# Custom_Stm_Board_v1_1.net
KiCad netlist of a schematic drawn in EasyEDA Pro
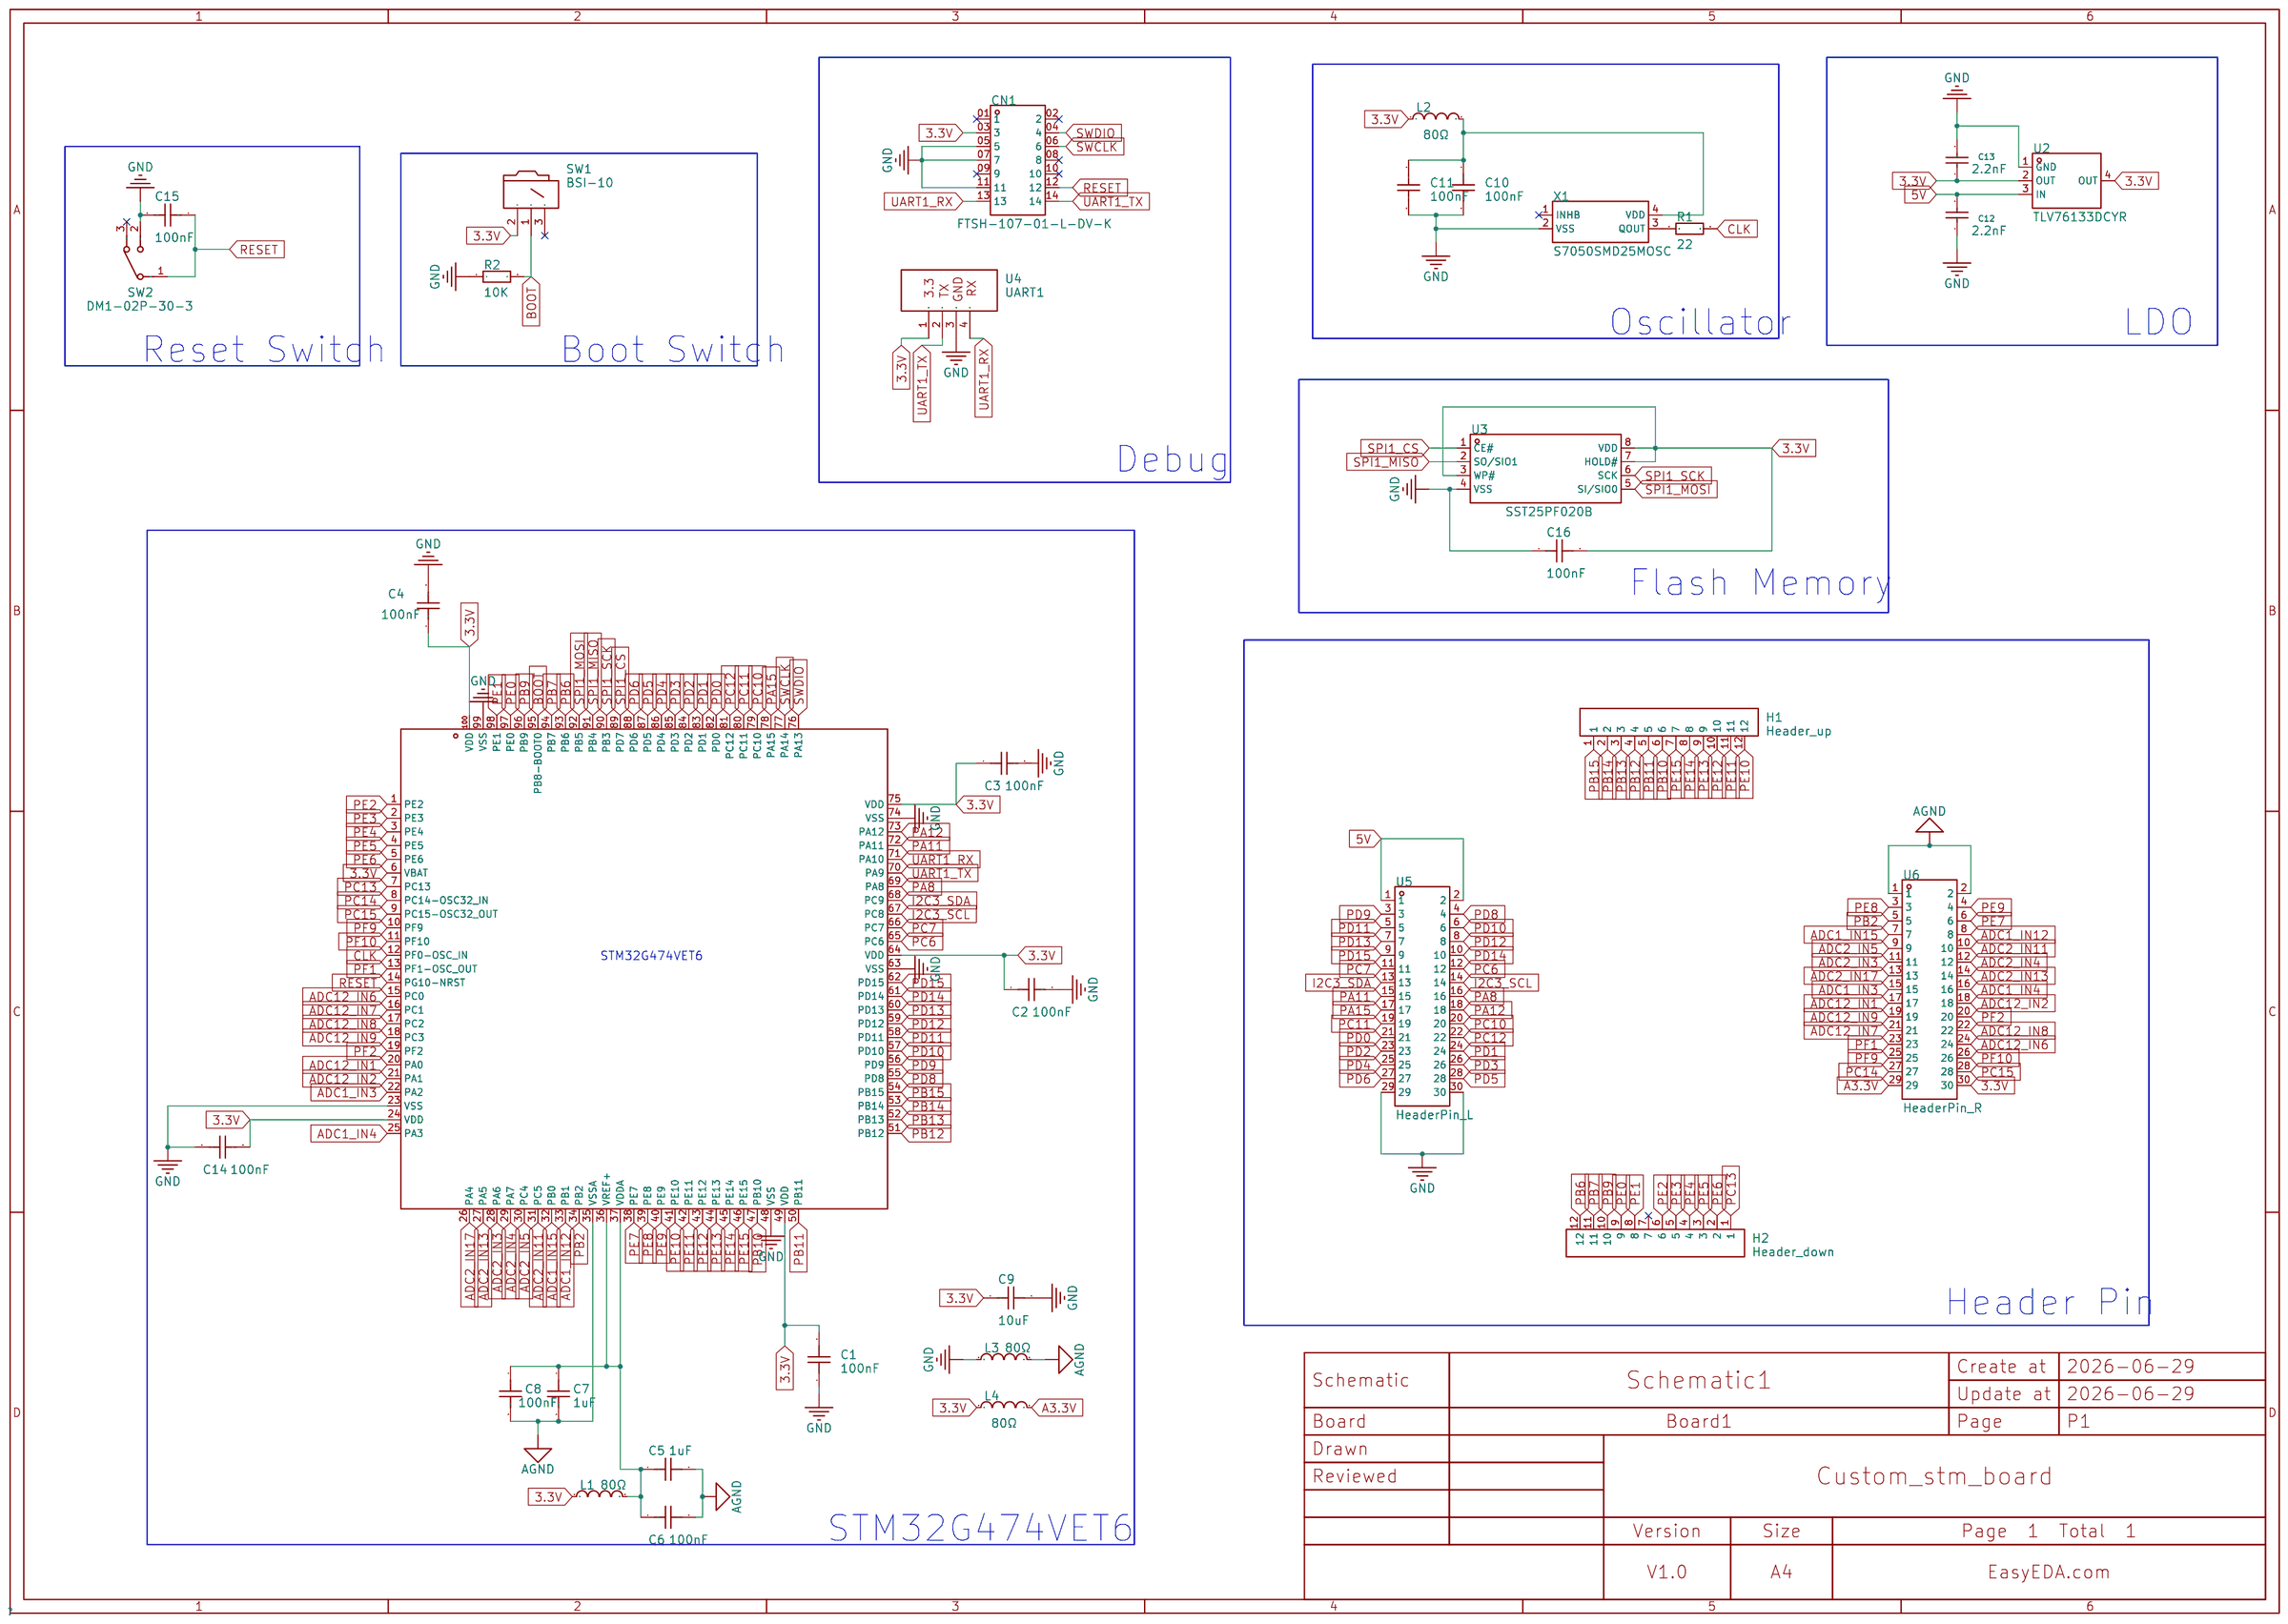
[diagram p0: schematic sheet]

(export (version "E")
  (design (tool "Eeschema 10.0.6"))
  (components
    (comp (ref "C1")
      (value "100nF")
      (footprint "easyedapro:C0603")
      (libsource (lib "easyedapro") (part "CAP"))
    )
    (comp (ref "C2")
      (value "100nF")
      (footprint "easyedapro:C0603")
      (libsource (lib "easyedapro") (part "CAP"))
    )
    (comp (ref "C3")
      (value "100nF")
      (footprint "easyedapro:C0603")
      (libsource (lib "easyedapro") (part "CAP"))
    )
    (comp (ref "C4")
      (value "100nF")
      (footprint "easyedapro:C0603")
      (libsource (lib "easyedapro") (part "CAP"))
    )
    (comp (ref "C5") (value "1uF") (footprint "easyedapro:C0603") (libsource (lib "easyedapro") (part "CAP")))
    (comp (ref "C6")
      (value "100nF")
      (footprint "easyedapro:C0603")
      (libsource (lib "easyedapro") (part "CAP"))
    )
    (comp (ref "C7") (value "1uF") (footprint "easyedapro:C0603") (libsource (lib "easyedapro") (part "CAP")))
    (comp (ref "C8")
      (value "100nF")
      (footprint "easyedapro:C0603")
      (libsource (lib "easyedapro") (part "CAP"))
    )
    (comp (ref "C9")
      (value "10uF")
      (footprint "easyedapro:C0603")
      (libsource (lib "easyedapro") (part "CAP"))
    )
    (comp (ref "C10")
      (value "100nF")
      (footprint "easyedapro:C0603")
      (libsource (lib "easyedapro") (part "CAP"))
    )
    (comp (ref "C11")
      (value "100nF")
      (footprint "easyedapro:C0603")
      (libsource (lib "easyedapro") (part "CAP"))
    )
    (comp (ref "C12")
      (value "2.2nF")
      (footprint "easyedapro:C0805")
      (fields
        (field (name "Manufacturer Part") "CL21B474KBFNNNE")
        (field (name "Manufacturer") "SAMSUNG(三星)")
      )
      (libsource (lib "easyedapro") (part "CL21B474KBFNNNE"))
    )
    (comp (ref "C13")
      (value "2.2nF")
      (footprint "easyedapro:C0805")
      (fields
        (field (name "Manufacturer Part") "CL21B474KBFNNNE")
        (field (name "Manufacturer") "SAMSUNG(三星)")
      )
      (libsource (lib "easyedapro") (part "CL21B474KBFNNNE"))
    )
    (comp (ref "C14")
      (value "100nF")
      (footprint "easyedapro:C0603")
      (libsource (lib "easyedapro") (part "CAP"))
    )
    (comp (ref "C15")
      (value "100nF")
      (footprint "easyedapro:C0603")
      (libsource (lib "easyedapro") (part "CAP"))
    )
    (comp (ref "C16")
      (value "100nF")
      (footprint "easyedapro:C0603")
      (libsource (lib "easyedapro") (part "CAP"))
    )
    (comp (ref "CN1")
      (value "FTSH-107-01-L-DV-K")
      (footprint "easyedapro:HDR-SMD_14P-P1.27_FTSH-107-01-L-DV-K")
      (fields (field (name "Manufacturer") "SAMTEC"))
      (libsource (lib "easyedapro") (part "FTSH-107-01-L-DV-K"))
    )
    (comp (ref "H1")
      (value "Header_up")
      (footprint "easyedapro:HDR-TH_12P-P2.54-V-M")
      (fields (field (name "Manufacturer Part") "PZ254V-11-12P") (field (name "Manufacturer") "XFCN(兴飞)"))
      (libsource (lib "easyedapro") (part "PZ254V-11-12P"))
    )
    (comp (ref "H2")
      (value "Header_down")
      (footprint "easyedapro:HDR-TH_12P-P2.54-V-M")
      (fields (field (name "Manufacturer") "XFCN(兴飞)"))
      (libsource (lib "easyedapro") (part "PZ254V-11-12P"))
    )
    (comp (ref "L1")
      (value "80Ω")
      (footprint "easyedapro:L0603")
      (fields (field (name "Manufacturer") "Sunlord(顺络)"))
      (libsource (lib "easyedapro") (part "GZ1608D601TF"))
    )
    (comp (ref "L2") (value "80Ω") (footprint "easyedapro:L0603") (libsource (lib "easyedapro") (part "电感")))
    (comp (ref "L3")
      (value "80Ω")
      (footprint "easyedapro:L0603")
      (fields (field (name "Manufacturer") "Sunlord(顺络)") (field (name "Tolerance") "±25%"))
      (libsource (lib "easyedapro") (part "GZ1608D601TF"))
    )
    (comp (ref "L4") (value "80Ω") (footprint "easyedapro:L0603") (libsource (lib "easyedapro") (part "电感")))
    (comp (ref "R1") (value "22") (footprint "easyedapro:R0603") (libsource (lib "easyedapro") (part "Res")))
    (comp (ref "R2") (value "10K") (footprint "easyedapro:R0603") (libsource (lib "easyedapro") (part "Res")))
    (comp (ref "SW1")
      (value "BSI-10")
      (footprint "easyedapro:SW-TH_BSI-10")
      (fields (field (name "Manufacturer") "SM Switch"))
      (libsource (lib "easyedapro") (part "BSI-10_C2985934"))
    )
    (comp (ref "SW2")
      (value "DM1-02P-30-3")
      (footprint "easyedapro:SW-TH_3P-L12.8-W5.8-P5.08_DM1-02P-30-3")
      (fields (field (name "Manufacturer") "SHOU HAN(首韩)"))
      (libsource (lib "easyedapro") (part "DM1-02P-30-3"))
    )
    (comp (ref "U1")
      (value "STM32G474VET6")
      (footprint "easyedapro:LQFP-100_L14.0-W14.0-P0.50-LS16.0-BL")
      (fields (field (name "Manufacturer") "ST(意法半导体)"))
      (libsource (lib "easyedapro") (part "STM32G474VET6"))
    )
    (comp (ref "U2")
      (value "TLV76133DCYR")
      (footprint "easyedapro:SOT-223-4_L6.5-W3.5-P2.30-LS7.0-TR")
      (fields (field (name "Manufacturer") "TI(德州仪器)"))
      (libsource (lib "easyedapro") (part "TLV76133DCYR"))
    )
    (comp (ref "U3")
      (value "SST25PF020B")
      (footprint "easyedapro:SOIC-8_L4.9-W3.9-P1.27-LS6.0-BL")
      (fields (field (name "Manufacturer") "MICROCHIP(美国微芯)"))
      (libsource (lib "easyedapro") (part "SST25PF020B-80-4C-SAE-T"))
    )
    (comp (ref "U4")
      (value "UART１")
      (libsource (lib "easyedapro") (part "DC_Main_to_Motordriver_Connector_4"))
    )
    (comp (ref "U5")
      (value "HeaderPin_L")
      (footprint "easyedapro:HDR-TH_30P-P2.54-V-M-R2-C15-S2.54-BL")
      (fields (field (name "Manufacturer") "XFCN(兴飞)"))
      (libsource (lib "easyedapro") (part "PZ254V-12-30P"))
    )
    (comp (ref "U6")
      (value "HeaderPin_R")
      (footprint "easyedapro:HDR-TH_30P-P2.54-V-M-R2-C15-S2.54-BL")
      (fields (field (name "Manufacturer") "XFCN(兴飞)"))
      (libsource (lib "easyedapro") (part "PZ254V-12-30P"))
    )
    (comp (ref "X1")
      (value "S7050SMD25MOSC")
      (footprint "easyedapro:OSC-SMD_4P-L7.0-W5.0-BL-2")
      (fields (field (name "Manufacturer") "SST(索斯特)"))
      (libsource (lib "easyedapro") (part "S7050SMD25MOSC"))
    )
  )
  (nets
    (net (code "1") (name "3.3V") (class "Default")
      (node (ref "C1") (pin "2") (pinfunction "2_2") (pintype "input"))
      (node (ref "C13") (pin "1") (pinfunction "1_1") (pintype "input"))
      (node (ref "C14") (pin "2") (pinfunction "2_2") (pintype "input"))
      (node (ref "C16") (pin "2") (pinfunction "2_2") (pintype "input"))
      (node (ref "C2") (pin "1") (pinfunction "1_1") (pintype "input"))
      (node (ref "C3") (pin "1") (pinfunction "1_1") (pintype "input"))
      (node (ref "C4") (pin "1") (pinfunction "1_1") (pintype "input"))
      (node (ref "C9") (pin "1") (pinfunction "1_1") (pintype "input"))
      (node (ref "CN1") (pin "03") (pinfunction "3_03") (pintype "unspecified"))
      (node (ref "L1") (pin "1") (pinfunction "1_1") (pintype "unspecified"))
      (node (ref "L2") (pin "1") (pinfunction "1_1") (pintype "input"))
      (node (ref "L4") (pin "1") (pinfunction "1_1") (pintype "input"))
      (node (ref "SW1") (pin "2") (pinfunction "2_2") (pintype "unspecified"))
      (node (ref "U1") (pin "100") (pinfunction "VDD_100") (pintype "unspecified"))
      (node (ref "U1") (pin "24") (pinfunction "VDD_24") (pintype "unspecified"))
      (node (ref "U1") (pin "49") (pinfunction "VDD_49") (pintype "unspecified"))
      (node (ref "U1") (pin "6") (pinfunction "VBAT_6") (pintype "unspecified"))
      (node (ref "U1") (pin "64") (pinfunction "VDD_64") (pintype "unspecified"))
      (node (ref "U1") (pin "75") (pinfunction "VDD_75") (pintype "unspecified"))
      (node (ref "U2") (pin "2") (pinfunction "OUT_2") (pintype "unspecified"))
      (node (ref "U2") (pin "4") (pinfunction "OUT_4") (pintype "unspecified"))
      (node (ref "U3") (pin "3") (pinfunction "WP#_3") (pintype "unspecified"))
      (node (ref "U3") (pin "7") (pinfunction "HOLD#_7") (pintype "unspecified"))
      (node (ref "U3") (pin "8") (pinfunction "VDD_8") (pintype "unspecified"))
      (node (ref "U4") (pin "1") (pinfunction "1_1") (pintype "input"))
      (node (ref "U6") (pin "30") (pinfunction "30_30") (pintype "unspecified"))
    )
    (net (code "2") (name "5V") (class "Default")
      (node (ref "C12") (pin "2") (pinfunction "2_2") (pintype "input"))
      (node (ref "U2") (pin "3") (pinfunction "IN_3") (pintype "unspecified"))
      (node (ref "U5") (pin "1") (pinfunction "1_1") (pintype "unspecified"))
      (node (ref "U5") (pin "2") (pinfunction "2_2") (pintype "unspecified"))
    )
    (net (code "3") (name "A3.3V") (class "Default")
      (node (ref "L4") (pin "2") (pinfunction "2_2") (pintype "input"))
      (node (ref "U6") (pin "29") (pinfunction "29_29") (pintype "unspecified"))
    )
    (net (code "4") (name "ADC1_IN3") (class "Default")
      (node (ref "U1") (pin "22") (pinfunction "PA2_22") (pintype "unspecified"))
      (node (ref "U6") (pin "15") (pinfunction "15_15") (pintype "unspecified"))
    )
    (net (code "5") (name "ADC1_IN4") (class "Default")
      (node (ref "U1") (pin "25") (pinfunction "PA3_25") (pintype "unspecified"))
      (node (ref "U6") (pin "16") (pinfunction "16_16") (pintype "unspecified"))
    )
    (net (code "6") (name "ADC1_IN12") (class "Default")
      (node (ref "U1") (pin "33") (pinfunction "PB1_33") (pintype "unspecified"))
      (node (ref "U6") (pin "8") (pinfunction "8_8") (pintype "unspecified"))
    )
    (net (code "7") (name "ADC1_IN15") (class "Default")
      (node (ref "U1") (pin "32") (pinfunction "PB0_32") (pintype "unspecified"))
      (node (ref "U6") (pin "7") (pinfunction "7_7") (pintype "unspecified"))
    )
    (net (code "8") (name "ADC2_IN3") (class "Default")
      (node (ref "U1") (pin "28") (pinfunction "PA6_28") (pintype "unspecified"))
      (node (ref "U6") (pin "11") (pinfunction "11_11") (pintype "unspecified"))
    )
    (net (code "9") (name "ADC2_IN4") (class "Default")
      (node (ref "U1") (pin "29") (pinfunction "PA7_29") (pintype "unspecified"))
      (node (ref "U6") (pin "12") (pinfunction "12_12") (pintype "unspecified"))
    )
    (net (code "10") (name "ADC2_IN5") (class "Default")
      (node (ref "U1") (pin "30") (pinfunction "PC4_30") (pintype "unspecified"))
      (node (ref "U6") (pin "9") (pinfunction "9_9") (pintype "unspecified"))
    )
    (net (code "11") (name "ADC2_IN11") (class "Default")
      (node (ref "U1") (pin "31") (pinfunction "PC5_31") (pintype "unspecified"))
      (node (ref "U6") (pin "10") (pinfunction "10_10") (pintype "unspecified"))
    )
    (net (code "12") (name "ADC2_IN13") (class "Default")
      (node (ref "U1") (pin "27") (pinfunction "PA5_27") (pintype "unspecified"))
      (node (ref "U6") (pin "14") (pinfunction "14_14") (pintype "unspecified"))
    )
    (net (code "13") (name "ADC2_IN17") (class "Default")
      (node (ref "U1") (pin "26") (pinfunction "PA4_26") (pintype "unspecified"))
      (node (ref "U6") (pin "13") (pinfunction "13_13") (pintype "unspecified"))
    )
    (net (code "14") (name "ADC12_IN1") (class "Default")
      (node (ref "U1") (pin "20") (pinfunction "PA0_20") (pintype "unspecified"))
      (node (ref "U6") (pin "17") (pinfunction "17_17") (pintype "unspecified"))
    )
    (net (code "15") (name "ADC12_IN2") (class "Default")
      (node (ref "U1") (pin "21") (pinfunction "PA1_21") (pintype "unspecified"))
      (node (ref "U6") (pin "18") (pinfunction "18_18") (pintype "unspecified"))
    )
    (net (code "16") (name "ADC12_IN6") (class "Default")
      (node (ref "U1") (pin "15") (pinfunction "PC0_15") (pintype "unspecified"))
      (node (ref "U6") (pin "24") (pinfunction "24_24") (pintype "unspecified"))
    )
    (net (code "17") (name "ADC12_IN7") (class "Default")
      (node (ref "U1") (pin "16") (pinfunction "PC1_16") (pintype "unspecified"))
      (node (ref "U6") (pin "21") (pinfunction "21_21") (pintype "unspecified"))
    )
    (net (code "18") (name "ADC12_IN8") (class "Default")
      (node (ref "U1") (pin "17") (pinfunction "PC2_17") (pintype "unspecified"))
      (node (ref "U6") (pin "22") (pinfunction "22_22") (pintype "unspecified"))
    )
    (net (code "19") (name "ADC12_IN9") (class "Default")
      (node (ref "U1") (pin "18") (pinfunction "PC3_18") (pintype "unspecified"))
      (node (ref "U6") (pin "19") (pinfunction "19_19") (pintype "unspecified"))
    )
    (net (code "20") (name "AGND") (class "Default")
      (node (ref "C5") (pin "2") (pinfunction "2_2") (pintype "input"))
      (node (ref "C6") (pin "2") (pinfunction "2_2") (pintype "input"))
      (node (ref "C7") (pin "2") (pinfunction "2_2") (pintype "input"))
      (node (ref "C8") (pin "2") (pinfunction "2_2") (pintype "input"))
      (node (ref "L3") (pin "2") (pinfunction "2_2") (pintype "unspecified"))
      (node (ref "U1") (pin "35") (pinfunction "VSSA_35") (pintype "unspecified"))
      (node (ref "U6") (pin "1") (pinfunction "1_1") (pintype "unspecified"))
      (node (ref "U6") (pin "2") (pinfunction "2_2") (pintype "unspecified"))
    )
    (net (code "21") (name "BOOT") (class "Default")
      (node (ref "R2") (pin "2") (pinfunction "2_2") (pintype "input"))
      (node (ref "SW1") (pin "1") (pinfunction "1_1") (pintype "unspecified"))
      (node (ref "U1") (pin "95") (pinfunction "PB8-BOOT0_95") (pintype "unspecified"))
    )
    (net (code "22") (name "CLK") (class "Default")
      (node (ref "R1") (pin "2") (pinfunction "2_2") (pintype "input"))
      (node (ref "U1") (pin "12") (pinfunction "PF0-OSC_IN_12") (pintype "unspecified"))
    )
    (net (code "23") (name "GND") (class "Default")
      (node (ref "C1") (pin "1") (pinfunction "1_1") (pintype "input"))
      (node (ref "C10") (pin "2") (pinfunction "2_2") (pintype "input"))
      (node (ref "C11") (pin "2") (pinfunction "2_2") (pintype "input"))
      (node (ref "C12") (pin "1") (pinfunction "1_1") (pintype "input"))
      (node (ref "C13") (pin "2") (pinfunction "2_2") (pintype "input"))
      (node (ref "C14") (pin "1") (pinfunction "1_1") (pintype "input"))
      (node (ref "C15") (pin "2") (pinfunction "2_2") (pintype "input"))
      (node (ref "C16") (pin "1") (pinfunction "1_1") (pintype "input"))
      (node (ref "C2") (pin "2") (pinfunction "2_2") (pintype "input"))
      (node (ref "C3") (pin "2") (pinfunction "2_2") (pintype "input"))
      (node (ref "C4") (pin "2") (pinfunction "2_2") (pintype "input"))
      (node (ref "C9") (pin "2") (pinfunction "2_2") (pintype "input"))
      (node (ref "CN1") (pin "05") (pinfunction "5_05") (pintype "unspecified"))
      (node (ref "CN1") (pin "07") (pinfunction "7_07") (pintype "unspecified"))
      (node (ref "CN1") (pin "11") (pinfunction "11_11") (pintype "unspecified"))
      (node (ref "L3") (pin "1") (pinfunction "1_1") (pintype "unspecified"))
      (node (ref "R2") (pin "1") (pinfunction "1_1") (pintype "input"))
      (node (ref "SW2") (pin "2") (pinfunction "ON_2") (pintype "input"))
      (node (ref "U1") (pin "23") (pinfunction "VSS_23") (pintype "unspecified"))
      (node (ref "U1") (pin "48") (pinfunction "VSS_48") (pintype "unspecified"))
      (node (ref "U1") (pin "63") (pinfunction "VSS_63") (pintype "unspecified"))
      (node (ref "U1") (pin "74") (pinfunction "VSS_74") (pintype "unspecified"))
      (node (ref "U1") (pin "99") (pinfunction "VSS_99") (pintype "unspecified"))
      (node (ref "U2") (pin "1") (pinfunction "GND_1") (pintype "unspecified"))
      (node (ref "U3") (pin "4") (pinfunction "VSS_4") (pintype "unspecified"))
      (node (ref "U4") (pin "3") (pinfunction "3_3") (pintype "input"))
      (node (ref "U5") (pin "29") (pinfunction "29_29") (pintype "unspecified"))
      (node (ref "U5") (pin "30") (pinfunction "30_30") (pintype "unspecified"))
      (node (ref "X1") (pin "2") (pinfunction "VSS_2") (pintype "unspecified"))
    )
    (net (code "24") (name "I2C3_SCL") (class "Default")
      (node (ref "U1") (pin "67") (pinfunction "PC8_67") (pintype "unspecified"))
      (node (ref "U5") (pin "14") (pinfunction "14_14") (pintype "unspecified"))
    )
    (net (code "25") (name "I2C3_SDA") (class "Default")
      (node (ref "U1") (pin "68") (pinfunction "PC9_68") (pintype "unspecified"))
      (node (ref "U5") (pin "13") (pinfunction "13_13") (pintype "unspecified"))
    )
    (net (code "26") (name "Net-(U1-VDDA)") (class "Default")
      (node (ref "C5") (pin "1") (pinfunction "1_1") (pintype "input"))
      (node (ref "C6") (pin "1") (pinfunction "1_1") (pintype "input"))
      (node (ref "C7") (pin "1") (pinfunction "1_1") (pintype "input"))
      (node (ref "C8") (pin "1") (pinfunction "1_1") (pintype "input"))
      (node (ref "L1") (pin "2") (pinfunction "2_2") (pintype "unspecified"))
      (node (ref "U1") (pin "36") (pinfunction "VREF+_36") (pintype "unspecified"))
      (node (ref "U1") (pin "37") (pinfunction "VDDA_37") (pintype "unspecified"))
    )
    (net (code "27") (name "Net-(X1-QOUT)") (class "Default")
      (node (ref "R1") (pin "1") (pinfunction "1_1") (pintype "input"))
      (node (ref "X1") (pin "3") (pinfunction "QOUT_3") (pintype "unspecified"))
    )
    (net (code "28") (name "Net-(X1-VDD)") (class "Default")
      (node (ref "C10") (pin "1") (pinfunction "1_1") (pintype "input"))
      (node (ref "C11") (pin "1") (pinfunction "1_1") (pintype "input"))
      (node (ref "L2") (pin "2") (pinfunction "2_2") (pintype "input"))
      (node (ref "X1") (pin "4") (pinfunction "VDD_4") (pintype "unspecified"))
    )
    (net (code "29") (name "PA8") (class "Default")
      (node (ref "U1") (pin "69") (pinfunction "PA8_69") (pintype "unspecified"))
      (node (ref "U5") (pin "16") (pinfunction "16_16") (pintype "unspecified"))
    )
    (net (code "30") (name "PA11") (class "Default")
      (node (ref "U1") (pin "72") (pinfunction "PA11_72") (pintype "unspecified"))
      (node (ref "U5") (pin "15") (pinfunction "15_15") (pintype "unspecified"))
    )
    (net (code "31") (name "PA12") (class "Default")
      (node (ref "U1") (pin "73") (pinfunction "PA12_73") (pintype "unspecified"))
      (node (ref "U5") (pin "18") (pinfunction "18_18") (pintype "unspecified"))
    )
    (net (code "32") (name "PA15") (class "Default")
      (node (ref "U1") (pin "78") (pinfunction "PA15_78") (pintype "unspecified"))
      (node (ref "U5") (pin "17") (pinfunction "17_17") (pintype "unspecified"))
    )
    (net (code "33") (name "PB2") (class "Default")
      (node (ref "U1") (pin "34") (pinfunction "PB2_34") (pintype "unspecified"))
      (node (ref "U6") (pin "5") (pinfunction "5_5") (pintype "unspecified"))
    )
    (net (code "34") (name "PB6") (class "Default")
      (node (ref "H2") (pin "12") (pinfunction "12_12") (pintype "unspecified"))
      (node (ref "U1") (pin "93") (pinfunction "PB6_93") (pintype "unspecified"))
    )
    (net (code "35") (name "PB7") (class "Default")
      (node (ref "H2") (pin "11") (pinfunction "11_11") (pintype "unspecified"))
      (node (ref "U1") (pin "94") (pinfunction "PB7_94") (pintype "unspecified"))
    )
    (net (code "36") (name "PB9") (class "Default")
      (node (ref "H2") (pin "10") (pinfunction "10_10") (pintype "unspecified"))
      (node (ref "U1") (pin "96") (pinfunction "PB9_96") (pintype "unspecified"))
    )
    (net (code "37") (name "PB10") (class "Default")
      (node (ref "H1") (pin "6") (pinfunction "6_6") (pintype "unspecified"))
      (node (ref "U1") (pin "47") (pinfunction "PB10_47") (pintype "unspecified"))
    )
    (net (code "38") (name "PB11") (class "Default")
      (node (ref "H1") (pin "5") (pinfunction "5_5") (pintype "unspecified"))
      (node (ref "U1") (pin "50") (pinfunction "PB11_50") (pintype "unspecified"))
    )
    (net (code "39") (name "PB12") (class "Default")
      (node (ref "H1") (pin "4") (pinfunction "4_4") (pintype "unspecified"))
      (node (ref "U1") (pin "51") (pinfunction "PB12_51") (pintype "unspecified"))
    )
    (net (code "40") (name "PB13") (class "Default")
      (node (ref "H1") (pin "3") (pinfunction "3_3") (pintype "unspecified"))
      (node (ref "U1") (pin "52") (pinfunction "PB13_52") (pintype "unspecified"))
    )
    (net (code "41") (name "PB14") (class "Default")
      (node (ref "H1") (pin "2") (pinfunction "2_2") (pintype "unspecified"))
      (node (ref "U1") (pin "53") (pinfunction "PB14_53") (pintype "unspecified"))
    )
    (net (code "42") (name "PB15") (class "Default")
      (node (ref "H1") (pin "1") (pinfunction "1_1") (pintype "unspecified"))
      (node (ref "U1") (pin "54") (pinfunction "PB15_54") (pintype "unspecified"))
    )
    (net (code "43") (name "PC6") (class "Default")
      (node (ref "U1") (pin "65") (pinfunction "PC6_65") (pintype "unspecified"))
      (node (ref "U5") (pin "12") (pinfunction "12_12") (pintype "unspecified"))
    )
    (net (code "44") (name "PC7") (class "Default")
      (node (ref "U1") (pin "66") (pinfunction "PC7_66") (pintype "unspecified"))
      (node (ref "U5") (pin "11") (pinfunction "11_11") (pintype "unspecified"))
    )
    (net (code "45") (name "PC10") (class "Default")
      (node (ref "U1") (pin "79") (pinfunction "PC10_79") (pintype "unspecified"))
      (node (ref "U5") (pin "20") (pinfunction "20_20") (pintype "unspecified"))
    )
    (net (code "46") (name "PC11") (class "Default")
      (node (ref "U1") (pin "80") (pinfunction "PC11_80") (pintype "unspecified"))
      (node (ref "U5") (pin "19") (pinfunction "19_19") (pintype "unspecified"))
    )
    (net (code "47") (name "PC12") (class "Default")
      (node (ref "U1") (pin "81") (pinfunction "PC12_81") (pintype "unspecified"))
      (node (ref "U5") (pin "22") (pinfunction "22_22") (pintype "unspecified"))
    )
    (net (code "48") (name "PC13") (class "Default")
      (node (ref "H2") (pin "1") (pinfunction "1_1") (pintype "unspecified"))
      (node (ref "U1") (pin "7") (pinfunction "PC13_7") (pintype "unspecified"))
    )
    (net (code "49") (name "PC14") (class "Default")
      (node (ref "U1") (pin "8") (pinfunction "PC14-OSC32_IN_8") (pintype "unspecified"))
      (node (ref "U6") (pin "27") (pinfunction "27_27") (pintype "unspecified"))
    )
    (net (code "50") (name "PC15") (class "Default")
      (node (ref "U1") (pin "9") (pinfunction "PC15-OSC32_OUT_9") (pintype "unspecified"))
      (node (ref "U6") (pin "28") (pinfunction "28_28") (pintype "unspecified"))
    )
    (net (code "51") (name "PD0") (class "Default")
      (node (ref "U1") (pin "82") (pinfunction "PD0_82") (pintype "unspecified"))
      (node (ref "U5") (pin "21") (pinfunction "21_21") (pintype "unspecified"))
    )
    (net (code "52") (name "PD1") (class "Default")
      (node (ref "U1") (pin "83") (pinfunction "PD1_83") (pintype "unspecified"))
      (node (ref "U5") (pin "24") (pinfunction "24_24") (pintype "unspecified"))
    )
    (net (code "53") (name "PD2") (class "Default")
      (node (ref "U1") (pin "84") (pinfunction "PD2_84") (pintype "unspecified"))
      (node (ref "U5") (pin "23") (pinfunction "23_23") (pintype "unspecified"))
    )
    (net (code "54") (name "PD3") (class "Default")
      (node (ref "U1") (pin "85") (pinfunction "PD3_85") (pintype "unspecified"))
      (node (ref "U5") (pin "26") (pinfunction "26_26") (pintype "unspecified"))
    )
    (net (code "55") (name "PD4") (class "Default")
      (node (ref "U1") (pin "86") (pinfunction "PD4_86") (pintype "unspecified"))
      (node (ref "U5") (pin "25") (pinfunction "25_25") (pintype "unspecified"))
    )
    (net (code "56") (name "PD5") (class "Default")
      (node (ref "U1") (pin "87") (pinfunction "PD5_87") (pintype "unspecified"))
      (node (ref "U5") (pin "28") (pinfunction "28_28") (pintype "unspecified"))
    )
    (net (code "57") (name "PD6") (class "Default")
      (node (ref "U1") (pin "88") (pinfunction "PD6_88") (pintype "unspecified"))
      (node (ref "U5") (pin "27") (pinfunction "27_27") (pintype "unspecified"))
    )
    (net (code "58") (name "PD8") (class "Default")
      (node (ref "U1") (pin "55") (pinfunction "PD8_55") (pintype "unspecified"))
      (node (ref "U5") (pin "4") (pinfunction "4_4") (pintype "unspecified"))
    )
    (net (code "59") (name "PD9") (class "Default")
      (node (ref "U1") (pin "56") (pinfunction "PD9_56") (pintype "unspecified"))
      (node (ref "U5") (pin "3") (pinfunction "3_3") (pintype "unspecified"))
    )
    (net (code "60") (name "PD10") (class "Default")
      (node (ref "U1") (pin "57") (pinfunction "PD10_57") (pintype "unspecified"))
      (node (ref "U5") (pin "6") (pinfunction "6_6") (pintype "unspecified"))
    )
    (net (code "61") (name "PD11") (class "Default")
      (node (ref "U1") (pin "58") (pinfunction "PD11_58") (pintype "unspecified"))
      (node (ref "U5") (pin "5") (pinfunction "5_5") (pintype "unspecified"))
    )
    (net (code "62") (name "PD12") (class "Default")
      (node (ref "U1") (pin "59") (pinfunction "PD12_59") (pintype "unspecified"))
      (node (ref "U5") (pin "8") (pinfunction "8_8") (pintype "unspecified"))
    )
    (net (code "63") (name "PD13") (class "Default")
      (node (ref "U1") (pin "60") (pinfunction "PD13_60") (pintype "unspecified"))
      (node (ref "U5") (pin "7") (pinfunction "7_7") (pintype "unspecified"))
    )
    (net (code "64") (name "PD14") (class "Default")
      (node (ref "U1") (pin "61") (pinfunction "PD14_61") (pintype "unspecified"))
      (node (ref "U5") (pin "10") (pinfunction "10_10") (pintype "unspecified"))
    )
    (net (code "65") (name "PD15") (class "Default")
      (node (ref "U1") (pin "62") (pinfunction "PD15_62") (pintype "unspecified"))
      (node (ref "U5") (pin "9") (pinfunction "9_9") (pintype "unspecified"))
    )
    (net (code "66") (name "PE0") (class "Default")
      (node (ref "H2") (pin "9") (pinfunction "9_9") (pintype "unspecified"))
      (node (ref "U1") (pin "97") (pinfunction "PE0_97") (pintype "unspecified"))
    )
    (net (code "67") (name "PE1") (class "Default")
      (node (ref "H2") (pin "8") (pinfunction "8_8") (pintype "unspecified"))
      (node (ref "U1") (pin "98") (pinfunction "PE1_98") (pintype "unspecified"))
    )
    (net (code "68") (name "PE2") (class "Default")
      (node (ref "H2") (pin "6") (pinfunction "6_6") (pintype "unspecified"))
      (node (ref "U1") (pin "1") (pinfunction "PE2_1") (pintype "unspecified"))
    )
    (net (code "69") (name "PE3") (class "Default")
      (node (ref "H2") (pin "5") (pinfunction "5_5") (pintype "unspecified"))
      (node (ref "U1") (pin "2") (pinfunction "PE3_2") (pintype "unspecified"))
    )
    (net (code "70") (name "PE4") (class "Default")
      (node (ref "H2") (pin "4") (pinfunction "4_4") (pintype "unspecified"))
      (node (ref "U1") (pin "3") (pinfunction "PE4_3") (pintype "unspecified"))
    )
    (net (code "71") (name "PE5") (class "Default")
      (node (ref "H2") (pin "3") (pinfunction "3_3") (pintype "unspecified"))
      (node (ref "U1") (pin "4") (pinfunction "PE5_4") (pintype "unspecified"))
    )
    (net (code "72") (name "PE6") (class "Default")
      (node (ref "H2") (pin "2") (pinfunction "2_2") (pintype "unspecified"))
      (node (ref "U1") (pin "5") (pinfunction "PE6_5") (pintype "unspecified"))
    )
    (net (code "73") (name "PE7") (class "Default")
      (node (ref "U1") (pin "38") (pinfunction "PE7_38") (pintype "unspecified"))
      (node (ref "U6") (pin "6") (pinfunction "6_6") (pintype "unspecified"))
    )
    (net (code "74") (name "PE8") (class "Default")
      (node (ref "U1") (pin "39") (pinfunction "PE8_39") (pintype "unspecified"))
      (node (ref "U6") (pin "3") (pinfunction "3_3") (pintype "unspecified"))
    )
    (net (code "75") (name "PE9") (class "Default")
      (node (ref "U1") (pin "40") (pinfunction "PE9_40") (pintype "unspecified"))
      (node (ref "U6") (pin "4") (pinfunction "4_4") (pintype "unspecified"))
    )
    (net (code "76") (name "PE10") (class "Default")
      (node (ref "H1") (pin "12") (pinfunction "12_12") (pintype "unspecified"))
      (node (ref "U1") (pin "41") (pinfunction "PE10_41") (pintype "unspecified"))
    )
    (net (code "77") (name "PE11") (class "Default")
      (node (ref "H1") (pin "11") (pinfunction "11_11") (pintype "unspecified"))
      (node (ref "U1") (pin "42") (pinfunction "PE11_42") (pintype "unspecified"))
    )
    (net (code "78") (name "PE12") (class "Default")
      (node (ref "H1") (pin "10") (pinfunction "10_10") (pintype "unspecified"))
      (node (ref "U1") (pin "43") (pinfunction "PE12_43") (pintype "unspecified"))
    )
    (net (code "79") (name "PE13") (class "Default")
      (node (ref "H1") (pin "9") (pinfunction "9_9") (pintype "unspecified"))
      (node (ref "U1") (pin "44") (pinfunction "PE13_44") (pintype "unspecified"))
    )
    (net (code "80") (name "PE14") (class "Default")
      (node (ref "H1") (pin "8") (pinfunction "8_8") (pintype "unspecified"))
      (node (ref "U1") (pin "45") (pinfunction "PE14_45") (pintype "unspecified"))
    )
    (net (code "81") (name "PE15") (class "Default")
      (node (ref "H1") (pin "7") (pinfunction "7_7") (pintype "unspecified"))
      (node (ref "U1") (pin "46") (pinfunction "PE15_46") (pintype "unspecified"))
    )
    (net (code "82") (name "PF1") (class "Default")
      (node (ref "U1") (pin "13") (pinfunction "PF1-OSC_OUT_13") (pintype "unspecified"))
      (node (ref "U6") (pin "23") (pinfunction "23_23") (pintype "unspecified"))
    )
    (net (code "83") (name "PF2") (class "Default")
      (node (ref "U1") (pin "19") (pinfunction "PF2_19") (pintype "unspecified"))
      (node (ref "U6") (pin "20") (pinfunction "20_20") (pintype "unspecified"))
    )
    (net (code "84") (name "PF9") (class "Default")
      (node (ref "U1") (pin "10") (pinfunction "PF9_10") (pintype "unspecified"))
      (node (ref "U6") (pin "25") (pinfunction "25_25") (pintype "unspecified"))
    )
    (net (code "85") (name "PF10") (class "Default")
      (node (ref "U1") (pin "11") (pinfunction "PF10_11") (pintype "unspecified"))
      (node (ref "U6") (pin "26") (pinfunction "26_26") (pintype "unspecified"))
    )
    (net (code "86") (name "RESET") (class "Default")
      (node (ref "C15") (pin "1") (pinfunction "1_1") (pintype "input"))
      (node (ref "CN1") (pin "12") (pinfunction "12_12") (pintype "unspecified"))
      (node (ref "SW2") (pin "1") (pinfunction "COM_1") (pintype "input"))
      (node (ref "U1") (pin "14") (pinfunction "PG10-NRST_14") (pintype "unspecified"))
    )
    (net (code "87") (name "SPI1_CS") (class "Default")
      (node (ref "U1") (pin "89") (pinfunction "PD7_89") (pintype "unspecified"))
      (node (ref "U3") (pin "1") (pinfunction "CE#_1") (pintype "unspecified"))
    )
    (net (code "88") (name "SPI1_MISO") (class "Default")
      (node (ref "U1") (pin "91") (pinfunction "PB4_91") (pintype "unspecified"))
      (node (ref "U3") (pin "2") (pinfunction "SO/SIO1_2") (pintype "unspecified"))
    )
    (net (code "89") (name "SPI1_MOSI") (class "Default")
      (node (ref "U1") (pin "92") (pinfunction "PB5_92") (pintype "unspecified"))
      (node (ref "U3") (pin "5") (pinfunction "SI/SIO0_5") (pintype "unspecified"))
    )
    (net (code "90") (name "SPI1_SCK") (class "Default")
      (node (ref "U1") (pin "90") (pinfunction "PB3_90") (pintype "unspecified"))
      (node (ref "U3") (pin "6") (pinfunction "SCK_6") (pintype "unspecified"))
    )
    (net (code "91") (name "SWCLK") (class "Default")
      (node (ref "CN1") (pin "06") (pinfunction "6_06") (pintype "unspecified"))
      (node (ref "U1") (pin "77") (pinfunction "PA14_77") (pintype "unspecified"))
    )
    (net (code "92") (name "SWDIO") (class "Default")
      (node (ref "CN1") (pin "04") (pinfunction "4_04") (pintype "unspecified"))
      (node (ref "U1") (pin "76") (pinfunction "PA13_76") (pintype "unspecified"))
    )
    (net (code "93") (name "UART1_RX") (class "Default")
      (node (ref "CN1") (pin "13") (pinfunction "13_13") (pintype "unspecified"))
      (node (ref "U1") (pin "71") (pinfunction "PA10_71") (pintype "unspecified"))
      (node (ref "U4") (pin "4") (pinfunction "4_4") (pintype "input"))
    )
    (net (code "94") (name "UART1_TX") (class "Default")
      (node (ref "CN1") (pin "14") (pinfunction "14_14") (pintype "unspecified"))
      (node (ref "U1") (pin "70") (pinfunction "PA9_70") (pintype "unspecified"))
      (node (ref "U4") (pin "2") (pinfunction "2_2") (pintype "input"))
    )
    (net (code "95") (name "unconnected-(CN1-1-Pad01)") (class "Default")
      (node (ref "CN1") (pin "01") (pinfunction "1_01") (pintype "unspecified+no_connect"))
    )
    (net (code "96") (name "unconnected-(CN1-2-Pad02)") (class "Default")
      (node (ref "CN1") (pin "02") (pinfunction "2_02") (pintype "unspecified+no_connect"))
    )
    (net (code "97") (name "unconnected-(CN1-8-Pad08)") (class "Default")
      (node (ref "CN1") (pin "08") (pinfunction "8_08") (pintype "unspecified+no_connect"))
    )
    (net (code "98") (name "unconnected-(CN1-9-Pad09)") (class "Default")
      (node (ref "CN1") (pin "09") (pinfunction "9_09") (pintype "unspecified+no_connect"))
    )
    (net (code "99") (name "unconnected-(CN1-Pad10)") (class "Default")
      (node (ref "CN1") (pin "10") (pinfunction "10_10") (pintype "unspecified+no_connect"))
    )
    (net (code "100") (name "unconnected-(H2-Pad7)") (class "Default")
      (node (ref "H2") (pin "7") (pinfunction "7_7") (pintype "unspecified+no_connect"))
    )
    (net (code "101") (name "unconnected-(SW1-Pad3)") (class "Default")
      (node (ref "SW1") (pin "3") (pinfunction "3_3") (pintype "unspecified+no_connect"))
    )
    (net (code "102") (name "unconnected-(SW2-NC-Pad3)") (class "Default")
      (node (ref "SW2") (pin "3") (pinfunction "NC_3") (pintype "input+no_connect"))
    )
    (net (code "103") (name "unconnected-(X1-INHB-Pad1)") (class "Default")
      (node (ref "X1") (pin "1") (pinfunction "INHB_1") (pintype "unspecified+no_connect"))
    )
  )
)
